# User_Input.net
KiCad netlist of a schematic drawn in EAGLE
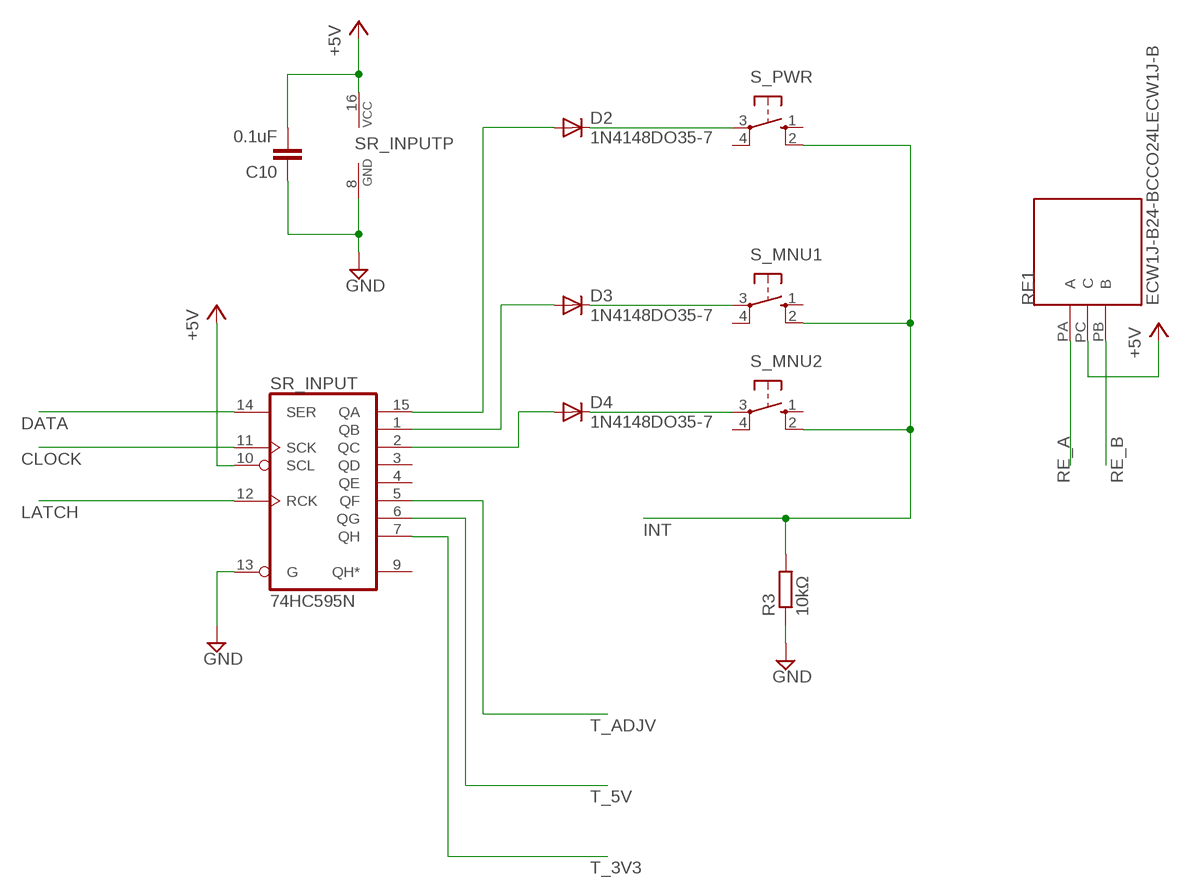
[diagram p0: schematic, sheet 1]

(export (version "E")
  (design (tool "Eeschema 10.0.6"))
  (components
    (comp (ref "C10")
      (value "0.1uF")
      (footprint "eagle-import:C025-025X050")
      (libsource (lib "eagle-import") (part "C-EU025-025X050"))
    )
    (comp (ref "D2")
      (value "1N4148DO35-7")
      (footprint "eagle-import:DO35-7")
      (libsource (lib "eagle-import") (part "1N4148DO35-7"))
    )
    (comp (ref "D3")
      (value "1N4148DO35-7")
      (footprint "eagle-import:DO35-7")
      (libsource (lib "eagle-import") (part "1N4148DO35-7"))
    )
    (comp (ref "D4")
      (value "1N4148DO35-7")
      (footprint "eagle-import:DO35-7")
      (libsource (lib "eagle-import") (part "1N4148DO35-7"))
    )
    (comp (ref "R3")
      (value "10kΩ")
      (footprint "eagle-import:0207_10")
      (libsource (lib "eagle-import") (part "R-EU_0207/10"))
    )
    (comp (ref "RE1")
      (value "ECW1J-B24-BCCO24LECW1J-B")
      (footprint "eagle-import:ECW1J-B")
      (libsource (lib "eagle-import") (part "ECW1J-B24-BCCO24LECW1J-B"))
    )
    (comp (ref "SR_INPUT")
      (value "74HC595N")
      (footprint "eagle-import:DIL16")
      (libsource (lib "eagle-import") (part "74595NHC"))
    )
    (comp (ref "S_MNU1")
      (value "10-XX")
      (footprint "eagle-import:B3F-10XX")
      (fields (field (name "MPN") "B3F-1000"))
      (libsource (lib "eagle-import") (part "10-XX"))
    )
    (comp (ref "S_MNU2")
      (value "10-XX")
      (footprint "eagle-import:B3F-10XX")
      (fields (field (name "MPN") "B3F-1000"))
      (libsource (lib "eagle-import") (part "10-XX"))
    )
    (comp (ref "S_PWR")
      (value "10-XX")
      (footprint "eagle-import:B3F-10XX")
      (fields (field (name "MPN") "B3F-1000"))
      (libsource (lib "eagle-import") (part "10-XX"))
    )
  )
  (nets
    (net (code "1") (name "+5V") (class "Default")
      (node (ref "C10") (pin "2") (pinfunction "2_2") (pintype "passive"))
      (node (ref "RE1") (pin "PC") (pinfunction "C_PC") (pintype "bidirectional"))
      (node (ref "SR_INPUT") (pin "10") (pinfunction "SCL_10") (pintype "input"))
      (node (ref "SR_INPUT") (pin "16") (pinfunction "VCC_16") (pintype "power_in"))
    )
    (net (code "2") (name "/CLOCK") (class "Default")
      (node (ref "SR_INPUT") (pin "11") (pinfunction "SCK_11") (pintype "input"))
    )
    (net (code "3") (name "/DATA") (class "Default")
      (node (ref "SR_INPUT") (pin "14") (pinfunction "SER_14") (pintype "input"))
    )
    (net (code "4") (name "/INT") (class "Default")
      (node (ref "R3") (pin "2") (pinfunction "2_2") (pintype "passive"))
      (node (ref "S_MNU1") (pin "2") (pinfunction "S1_2") (pintype "passive"))
      (node (ref "S_MNU2") (pin "2") (pinfunction "S1_2") (pintype "passive"))
      (node (ref "S_PWR") (pin "2") (pinfunction "S1_2") (pintype "passive"))
    )
    (net (code "5") (name "/LATCH") (class "Default")
      (node (ref "SR_INPUT") (pin "12") (pinfunction "RCK_12") (pintype "input"))
    )
    (net (code "6") (name "/RE_A") (class "Default")
      (node (ref "RE1") (pin "PA") (pinfunction "A_PA") (pintype "bidirectional"))
    )
    (net (code "7") (name "/RE_B") (class "Default")
      (node (ref "RE1") (pin "PB") (pinfunction "B_PB") (pintype "bidirectional"))
    )
    (net (code "8") (name "/T_3V3") (class "Default")
      (node (ref "SR_INPUT") (pin "7") (pinfunction "QH_7") (pintype "tri_state"))
    )
    (net (code "9") (name "/T_5V") (class "Default")
      (node (ref "SR_INPUT") (pin "6") (pinfunction "QG_6") (pintype "tri_state"))
    )
    (net (code "10") (name "/T_ADJV") (class "Default")
      (node (ref "SR_INPUT") (pin "5") (pinfunction "QF_5") (pintype "tri_state"))
    )
    (net (code "11") (name "GND") (class "Default")
      (node (ref "C10") (pin "1") (pinfunction "1_1") (pintype "passive"))
      (node (ref "R3") (pin "1") (pinfunction "1_1") (pintype "passive"))
      (node (ref "SR_INPUT") (pin "13") (pinfunction "G_13") (pintype "input"))
      (node (ref "SR_INPUT") (pin "8") (pinfunction "GND_8") (pintype "power_in"))
    )
    (net (code "12") (name "Net-(SR_INPUTA-QA)") (class "Default")
      (node (ref "D2") (pin "A") (pinfunction "A_A") (pintype "passive"))
      (node (ref "SR_INPUT") (pin "15") (pinfunction "QA_15") (pintype "tri_state"))
    )
    (net (code "13") (name "Net-(SR_INPUTA-QB)") (class "Default")
      (node (ref "D3") (pin "A") (pinfunction "A_A") (pintype "passive"))
      (node (ref "SR_INPUT") (pin "1") (pinfunction "QB_1") (pintype "tri_state"))
    )
    (net (code "14") (name "Net-(SR_INPUTA-QC)") (class "Default")
      (node (ref "D4") (pin "A") (pinfunction "A_A") (pintype "passive"))
      (node (ref "SR_INPUT") (pin "2") (pinfunction "QC_2") (pintype "tri_state"))
    )
    (net (code "15") (name "Net-(S_MNU1-P)") (class "Default")
      (node (ref "D3") (pin "C") (pinfunction "C_C") (pintype "passive"))
      (node (ref "S_MNU1") (pin "3") (pinfunction "P_3") (pintype "passive"))
    )
    (net (code "16") (name "Net-(S_MNU2-P)") (class "Default")
      (node (ref "D4") (pin "C") (pinfunction "C_C") (pintype "passive"))
      (node (ref "S_MNU2") (pin "3") (pinfunction "P_3") (pintype "passive"))
    )
    (net (code "17") (name "Net-(S_PWR-P)") (class "Default")
      (node (ref "D2") (pin "C") (pinfunction "C_C") (pintype "passive"))
      (node (ref "S_PWR") (pin "3") (pinfunction "P_3") (pintype "passive"))
    )
    (net (code "18") (name "unconnected-(SR_INPUTA-QD-Pad3)") (class "Default")
      (node (ref "SR_INPUT") (pin "3") (pinfunction "QD_3") (pintype "tri_state"))
    )
    (net (code "19") (name "unconnected-(SR_INPUTA-QE-Pad4)") (class "Default")
      (node (ref "SR_INPUT") (pin "4") (pinfunction "QE_4") (pintype "tri_state"))
    )
    (net (code "20") (name "unconnected-(SR_INPUTA-QH*-Pad9)") (class "Default")
      (node (ref "SR_INPUT") (pin "9") (pinfunction "QH*_9") (pintype "tri_state"))
    )
    (net (code "21") (name "unconnected-(S_MNU1-P1-Pad4)") (class "Default")
      (node (ref "S_MNU1") (pin "4") (pinfunction "P1_4") (pintype "passive"))
    )
    (net (code "22") (name "unconnected-(S_MNU1-S-Pad1)") (class "Default")
      (node (ref "S_MNU1") (pin "1") (pinfunction "S_1") (pintype "passive"))
    )
    (net (code "23") (name "unconnected-(S_MNU2-P1-Pad4)") (class "Default")
      (node (ref "S_MNU2") (pin "4") (pinfunction "P1_4") (pintype "passive"))
    )
    (net (code "24") (name "unconnected-(S_MNU2-S-Pad1)") (class "Default")
      (node (ref "S_MNU2") (pin "1") (pinfunction "S_1") (pintype "passive"))
    )
    (net (code "25") (name "unconnected-(S_PWR-P1-Pad4)") (class "Default")
      (node (ref "S_PWR") (pin "4") (pinfunction "P1_4") (pintype "passive"))
    )
    (net (code "26") (name "unconnected-(S_PWR-S-Pad1)") (class "Default")
      (node (ref "S_PWR") (pin "1") (pinfunction "S_1") (pintype "passive"))
    )
  )
)
